# 10_ZynTra-Connectors.net
KiCad netlist of a schematic drawn in Altium Designer
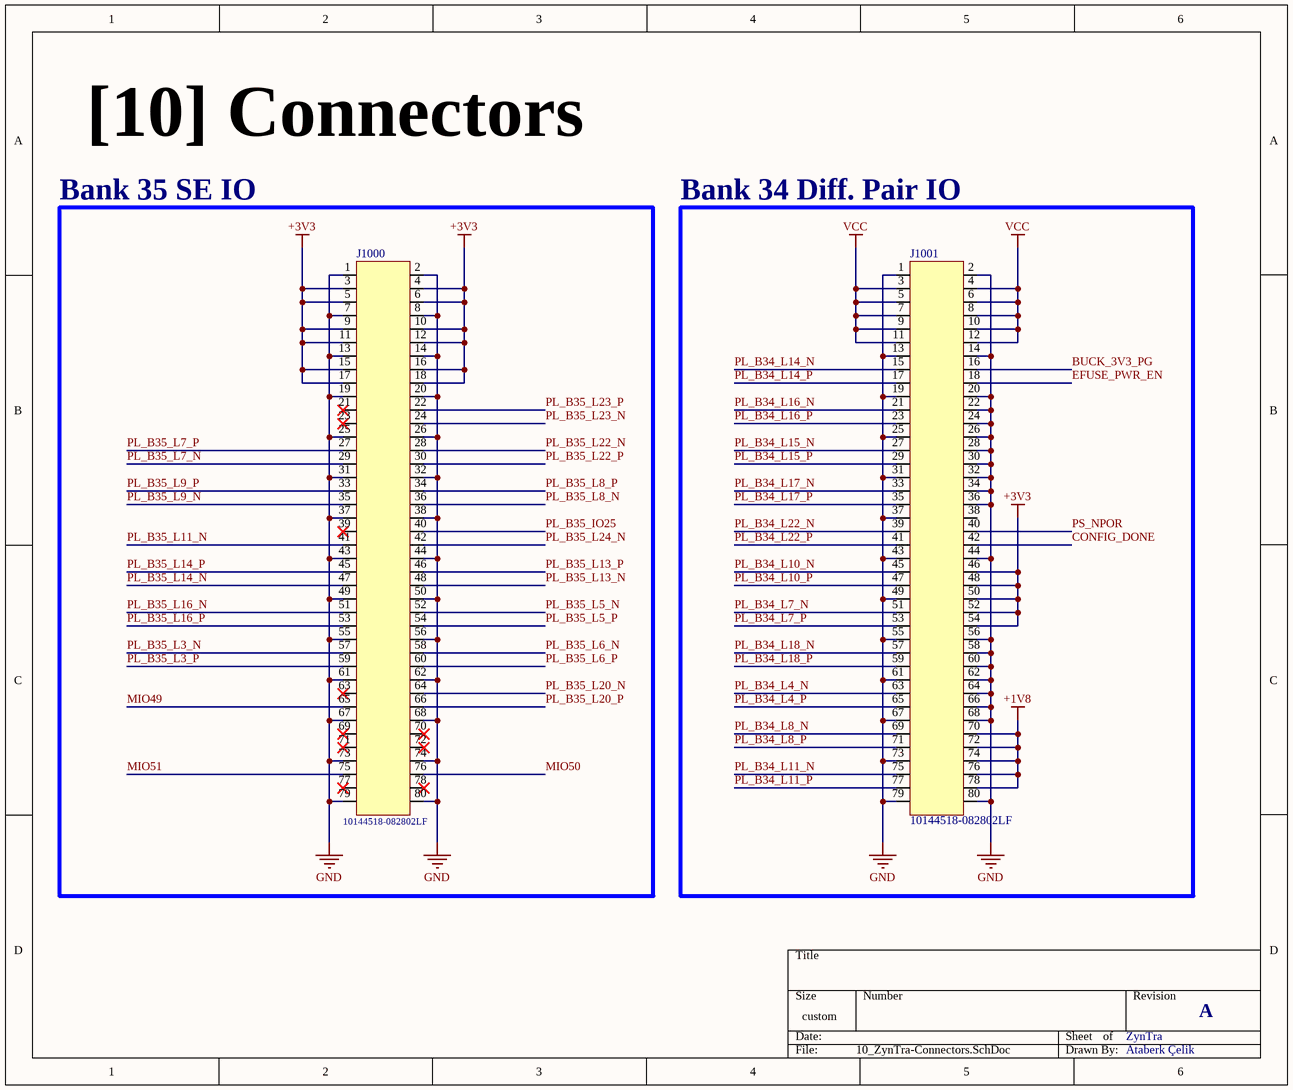
[diagram p0: 10_ZynTra-Connectors.SchDoc]

(export (version "E")
  (design (tool "Eeschema 10.0.6"))
  (components
    (comp (ref "J1000")
      (value "10144518-082802LF")
      (footprint "10144518-082802LF")
      (description "BergStak® Lite 0.80mm, Board-to-Board Connector, 80 Positions, Dual Row, Vertical Header")
      (fields (field (name "MANUFACTURER") "Amphenol"))
      (libsource (lib "Schematic-Lib-PhilsLab") (part "10144518-082802LF"))
    )
    (comp (ref "J1001")
      (value "10144518-082802LF")
      (footprint "10144518-082802LF")
      (description "BergStak® Lite 0.80mm, Board-to-Board Connector, 80 Positions, Dual Row, Vertical Header")
      (fields (field (name "MANUFACTURER") "Amphenol"))
      (libsource (lib "Schematic-Lib-PhilsLab") (part "10144518-082802LF"))
    )
  )
  (nets
    (net (code "1") (name "+1V8") (class "Default")
      (node (ref "J1001") (pin "70") (pintype "passive"))
      (node (ref "J1001") (pin "72") (pintype "passive"))
      (node (ref "J1001") (pin "74") (pintype "passive"))
      (node (ref "J1001") (pin "76") (pintype "passive"))
      (node (ref "J1001") (pin "78") (pintype "passive"))
    )
    (net (code "2") (name "+3V3") (class "Default")
      (node (ref "J1000") (pin "10") (pintype "passive"))
      (node (ref "J1000") (pin "11") (pintype "passive"))
      (node (ref "J1000") (pin "12") (pintype "passive"))
      (node (ref "J1000") (pin "15") (pintype "passive"))
      (node (ref "J1000") (pin "16") (pintype "passive"))
      (node (ref "J1000") (pin "17") (pintype "passive"))
      (node (ref "J1000") (pin "18") (pintype "passive"))
      (node (ref "J1000") (pin "3") (pintype "passive"))
      (node (ref "J1000") (pin "4") (pintype "passive"))
      (node (ref "J1000") (pin "5") (pintype "passive"))
      (node (ref "J1000") (pin "6") (pintype "passive"))
      (node (ref "J1000") (pin "9") (pintype "passive"))
      (node (ref "J1001") (pin "46") (pintype "passive"))
      (node (ref "J1001") (pin "48") (pintype "passive"))
      (node (ref "J1001") (pin "50") (pintype "passive"))
      (node (ref "J1001") (pin "52") (pintype "passive"))
      (node (ref "J1001") (pin "54") (pintype "passive"))
    )
    (net (code "3") (name "/BUCK_3V3_PG") (class "Default")
      (node (ref "J1001") (pin "16") (pintype "passive"))
    )
    (net (code "4") (name "/CONFIG_DONE") (class "Default")
      (node (ref "J1001") (pin "42") (pintype "passive"))
    )
    (net (code "5") (name "/EFUSE_PWR_EN") (class "Default")
      (node (ref "J1001") (pin "18") (pintype "passive"))
    )
    (net (code "6") (name "/MIO49") (class "Default") (node (ref "J1000") (pin "65") (pintype "passive")))
    (net (code "7") (name "/MIO50") (class "Default") (node (ref "J1000") (pin "76") (pintype "passive")))
    (net (code "8") (name "/MIO51") (class "Default") (node (ref "J1000") (pin "75") (pintype "passive")))
    (net (code "9") (name "/PL_B34_L4_N") (class "Default")
      (node (ref "J1001") (pin "63") (pintype "passive"))
    )
    (net (code "10") (name "/PL_B34_L4_P") (class "Default")
      (node (ref "J1001") (pin "65") (pintype "passive"))
    )
    (net (code "11") (name "/PL_B34_L7_N") (class "Default")
      (node (ref "J1001") (pin "51") (pintype "passive"))
    )
    (net (code "12") (name "/PL_B34_L7_P") (class "Default")
      (node (ref "J1001") (pin "53") (pintype "passive"))
    )
    (net (code "13") (name "/PL_B34_L8_N") (class "Default")
      (node (ref "J1001") (pin "69") (pintype "passive"))
    )
    (net (code "14") (name "/PL_B34_L8_P") (class "Default")
      (node (ref "J1001") (pin "71") (pintype "passive"))
    )
    (net (code "15") (name "/PL_B34_L10_N") (class "Default")
      (node (ref "J1001") (pin "45") (pintype "passive"))
    )
    (net (code "16") (name "/PL_B34_L10_P") (class "Default")
      (node (ref "J1001") (pin "47") (pintype "passive"))
    )
    (net (code "17") (name "/PL_B34_L11_N") (class "Default")
      (node (ref "J1001") (pin "75") (pintype "passive"))
    )
    (net (code "18") (name "/PL_B34_L11_P") (class "Default")
      (node (ref "J1001") (pin "77") (pintype "passive"))
    )
    (net (code "19") (name "/PL_B34_L14_N") (class "Default")
      (node (ref "J1001") (pin "15") (pintype "passive"))
    )
    (net (code "20") (name "/PL_B34_L14_P") (class "Default")
      (node (ref "J1001") (pin "17") (pintype "passive"))
    )
    (net (code "21") (name "/PL_B34_L15_N") (class "Default")
      (node (ref "J1001") (pin "27") (pintype "passive"))
    )
    (net (code "22") (name "/PL_B34_L15_P") (class "Default")
      (node (ref "J1001") (pin "29") (pintype "passive"))
    )
    (net (code "23") (name "/PL_B34_L16_N") (class "Default")
      (node (ref "J1001") (pin "21") (pintype "passive"))
    )
    (net (code "24") (name "/PL_B34_L16_P") (class "Default")
      (node (ref "J1001") (pin "23") (pintype "passive"))
    )
    (net (code "25") (name "/PL_B34_L17_N") (class "Default")
      (node (ref "J1001") (pin "33") (pintype "passive"))
    )
    (net (code "26") (name "/PL_B34_L17_P") (class "Default")
      (node (ref "J1001") (pin "35") (pintype "passive"))
    )
    (net (code "27") (name "/PL_B34_L18_N") (class "Default")
      (node (ref "J1001") (pin "57") (pintype "passive"))
    )
    (net (code "28") (name "/PL_B34_L18_P") (class "Default")
      (node (ref "J1001") (pin "59") (pintype "passive"))
    )
    (net (code "29") (name "/PL_B34_L22_N") (class "Default")
      (node (ref "J1001") (pin "39") (pintype "passive"))
    )
    (net (code "30") (name "/PL_B34_L22_P") (class "Default")
      (node (ref "J1001") (pin "41") (pintype "passive"))
    )
    (net (code "31") (name "/PL_B35_IO25") (class "Default")
      (node (ref "J1000") (pin "40") (pintype "passive"))
    )
    (net (code "32") (name "/PL_B35_L3_N") (class "Default")
      (node (ref "J1000") (pin "57") (pintype "passive"))
    )
    (net (code "33") (name "/PL_B35_L3_P") (class "Default")
      (node (ref "J1000") (pin "59") (pintype "passive"))
    )
    (net (code "34") (name "/PL_B35_L5_N") (class "Default")
      (node (ref "J1000") (pin "52") (pintype "passive"))
    )
    (net (code "35") (name "/PL_B35_L5_P") (class "Default")
      (node (ref "J1000") (pin "54") (pintype "passive"))
    )
    (net (code "36") (name "/PL_B35_L6_N") (class "Default")
      (node (ref "J1000") (pin "58") (pintype "passive"))
    )
    (net (code "37") (name "/PL_B35_L6_P") (class "Default")
      (node (ref "J1000") (pin "60") (pintype "passive"))
    )
    (net (code "38") (name "/PL_B35_L7_N") (class "Default")
      (node (ref "J1000") (pin "29") (pintype "passive"))
    )
    (net (code "39") (name "/PL_B35_L7_P") (class "Default")
      (node (ref "J1000") (pin "27") (pintype "passive"))
    )
    (net (code "40") (name "/PL_B35_L8_N") (class "Default")
      (node (ref "J1000") (pin "36") (pintype "passive"))
    )
    (net (code "41") (name "/PL_B35_L8_P") (class "Default")
      (node (ref "J1000") (pin "34") (pintype "passive"))
    )
    (net (code "42") (name "/PL_B35_L9_N") (class "Default")
      (node (ref "J1000") (pin "35") (pintype "passive"))
    )
    (net (code "43") (name "/PL_B35_L9_P") (class "Default")
      (node (ref "J1000") (pin "33") (pintype "passive"))
    )
    (net (code "44") (name "/PL_B35_L11_N") (class "Default")
      (node (ref "J1000") (pin "41") (pintype "passive"))
    )
    (net (code "45") (name "/PL_B35_L13_N") (class "Default")
      (node (ref "J1000") (pin "48") (pintype "passive"))
    )
    (net (code "46") (name "/PL_B35_L13_P") (class "Default")
      (node (ref "J1000") (pin "46") (pintype "passive"))
    )
    (net (code "47") (name "/PL_B35_L14_N") (class "Default")
      (node (ref "J1000") (pin "47") (pintype "passive"))
    )
    (net (code "48") (name "/PL_B35_L14_P") (class "Default")
      (node (ref "J1000") (pin "45") (pintype "passive"))
    )
    (net (code "49") (name "/PL_B35_L16_N") (class "Default")
      (node (ref "J1000") (pin "51") (pintype "passive"))
    )
    (net (code "50") (name "/PL_B35_L16_P") (class "Default")
      (node (ref "J1000") (pin "53") (pintype "passive"))
    )
    (net (code "51") (name "/PL_B35_L20_N") (class "Default")
      (node (ref "J1000") (pin "64") (pintype "passive"))
    )
    (net (code "52") (name "/PL_B35_L20_P") (class "Default")
      (node (ref "J1000") (pin "66") (pintype "passive"))
    )
    (net (code "53") (name "/PL_B35_L22_N") (class "Default")
      (node (ref "J1000") (pin "28") (pintype "passive"))
    )
    (net (code "54") (name "/PL_B35_L22_P") (class "Default")
      (node (ref "J1000") (pin "30") (pintype "passive"))
    )
    (net (code "55") (name "/PL_B35_L23_N") (class "Default")
      (node (ref "J1000") (pin "24") (pintype "passive"))
    )
    (net (code "56") (name "/PL_B35_L23_P") (class "Default")
      (node (ref "J1000") (pin "22") (pintype "passive"))
    )
    (net (code "57") (name "/PL_B35_L24_N") (class "Default")
      (node (ref "J1000") (pin "42") (pintype "passive"))
    )
    (net (code "58") (name "/PS_NPOR") (class "Default") (node (ref "J1001") (pin "40") (pintype "passive")))
    (net (code "59") (name "GND") (class "Default")
      (node (ref "J1000") (pin "1") (pintype "passive"))
      (node (ref "J1000") (pin "13") (pintype "passive"))
      (node (ref "J1000") (pin "14") (pintype "passive"))
      (node (ref "J1000") (pin "19") (pintype "passive"))
      (node (ref "J1000") (pin "2") (pintype "passive"))
      (node (ref "J1000") (pin "20") (pintype "passive"))
      (node (ref "J1000") (pin "25") (pintype "passive"))
      (node (ref "J1000") (pin "26") (pintype "passive"))
      (node (ref "J1000") (pin "31") (pintype "passive"))
      (node (ref "J1000") (pin "32") (pintype "passive"))
      (node (ref "J1000") (pin "37") (pintype "passive"))
      (node (ref "J1000") (pin "38") (pintype "passive"))
      (node (ref "J1000") (pin "43") (pintype "passive"))
      (node (ref "J1000") (pin "44") (pintype "passive"))
      (node (ref "J1000") (pin "49") (pintype "passive"))
      (node (ref "J1000") (pin "50") (pintype "passive"))
      (node (ref "J1000") (pin "55") (pintype "passive"))
      (node (ref "J1000") (pin "56") (pintype "passive"))
      (node (ref "J1000") (pin "61") (pintype "passive"))
      (node (ref "J1000") (pin "62") (pintype "passive"))
      (node (ref "J1000") (pin "67") (pintype "passive"))
      (node (ref "J1000") (pin "68") (pintype "passive"))
      (node (ref "J1000") (pin "7") (pintype "passive"))
      (node (ref "J1000") (pin "73") (pintype "passive"))
      (node (ref "J1000") (pin "74") (pintype "passive"))
      (node (ref "J1000") (pin "79") (pintype "passive"))
      (node (ref "J1000") (pin "8") (pintype "passive"))
      (node (ref "J1000") (pin "80") (pintype "passive"))
      (node (ref "J1001") (pin "1") (pintype "passive"))
      (node (ref "J1001") (pin "13") (pintype "passive"))
      (node (ref "J1001") (pin "14") (pintype "passive"))
      (node (ref "J1001") (pin "19") (pintype "passive"))
      (node (ref "J1001") (pin "2") (pintype "passive"))
      (node (ref "J1001") (pin "20") (pintype "passive"))
      (node (ref "J1001") (pin "22") (pintype "passive"))
      (node (ref "J1001") (pin "24") (pintype "passive"))
      (node (ref "J1001") (pin "25") (pintype "passive"))
      (node (ref "J1001") (pin "26") (pintype "passive"))
      (node (ref "J1001") (pin "28") (pintype "passive"))
      (node (ref "J1001") (pin "30") (pintype "passive"))
      (node (ref "J1001") (pin "31") (pintype "passive"))
      (node (ref "J1001") (pin "32") (pintype "passive"))
      (node (ref "J1001") (pin "34") (pintype "passive"))
      (node (ref "J1001") (pin "36") (pintype "passive"))
      (node (ref "J1001") (pin "37") (pintype "passive"))
      (node (ref "J1001") (pin "43") (pintype "passive"))
      (node (ref "J1001") (pin "44") (pintype "passive"))
      (node (ref "J1001") (pin "49") (pintype "passive"))
      (node (ref "J1001") (pin "55") (pintype "passive"))
      (node (ref "J1001") (pin "56") (pintype "passive"))
      (node (ref "J1001") (pin "58") (pintype "passive"))
      (node (ref "J1001") (pin "60") (pintype "passive"))
      (node (ref "J1001") (pin "61") (pintype "passive"))
      (node (ref "J1001") (pin "62") (pintype "passive"))
      (node (ref "J1001") (pin "64") (pintype "passive"))
      (node (ref "J1001") (pin "66") (pintype "passive"))
      (node (ref "J1001") (pin "67") (pintype "passive"))
      (node (ref "J1001") (pin "68") (pintype "passive"))
      (node (ref "J1001") (pin "73") (pintype "passive"))
      (node (ref "J1001") (pin "79") (pintype "passive"))
      (node (ref "J1001") (pin "80") (pintype "passive"))
    )
    (net (code "60") (name "VCC") (class "Default")
      (node (ref "J1001") (pin "10") (pintype "passive"))
      (node (ref "J1001") (pin "11") (pintype "passive"))
      (node (ref "J1001") (pin "12") (pintype "passive"))
      (node (ref "J1001") (pin "3") (pintype "passive"))
      (node (ref "J1001") (pin "4") (pintype "passive"))
      (node (ref "J1001") (pin "5") (pintype "passive"))
      (node (ref "J1001") (pin "6") (pintype "passive"))
      (node (ref "J1001") (pin "7") (pintype "passive"))
      (node (ref "J1001") (pin "8") (pintype "passive"))
      (node (ref "J1001") (pin "9") (pintype "passive"))
    )
    (net (code "61") (name "unconnected-(J1000-Pad21)") (class "Default")
      (node (ref "J1000") (pin "21") (pintype "passive+no_connect"))
    )
    (net (code "62") (name "unconnected-(J1000-Pad23)") (class "Default")
      (node (ref "J1000") (pin "23") (pintype "passive+no_connect"))
    )
    (net (code "63") (name "unconnected-(J1000-Pad39)") (class "Default")
      (node (ref "J1000") (pin "39") (pintype "passive+no_connect"))
    )
    (net (code "64") (name "unconnected-(J1000-Pad63)") (class "Default")
      (node (ref "J1000") (pin "63") (pintype "passive+no_connect"))
    )
    (net (code "65") (name "unconnected-(J1000-Pad69)") (class "Default")
      (node (ref "J1000") (pin "69") (pintype "passive+no_connect"))
    )
    (net (code "66") (name "unconnected-(J1000-Pad70)") (class "Default")
      (node (ref "J1000") (pin "70") (pintype "passive+no_connect"))
    )
    (net (code "67") (name "unconnected-(J1000-Pad71)") (class "Default")
      (node (ref "J1000") (pin "71") (pintype "passive+no_connect"))
    )
    (net (code "68") (name "unconnected-(J1000-Pad72)") (class "Default")
      (node (ref "J1000") (pin "72") (pintype "passive+no_connect"))
    )
    (net (code "69") (name "unconnected-(J1000-Pad77)") (class "Default")
      (node (ref "J1000") (pin "77") (pintype "passive+no_connect"))
    )
    (net (code "70") (name "unconnected-(J1000-Pad78)") (class "Default")
      (node (ref "J1000") (pin "78") (pintype "passive+no_connect"))
    )
    (net (code "71") (name "unconnected-(J1001-Pad38)") (class "Default")
      (node (ref "J1001") (pin "38") (pintype "passive"))
    )
  )
)
